# EFM32_2.net
KiCad netlist of a schematic drawn in Altium Designer
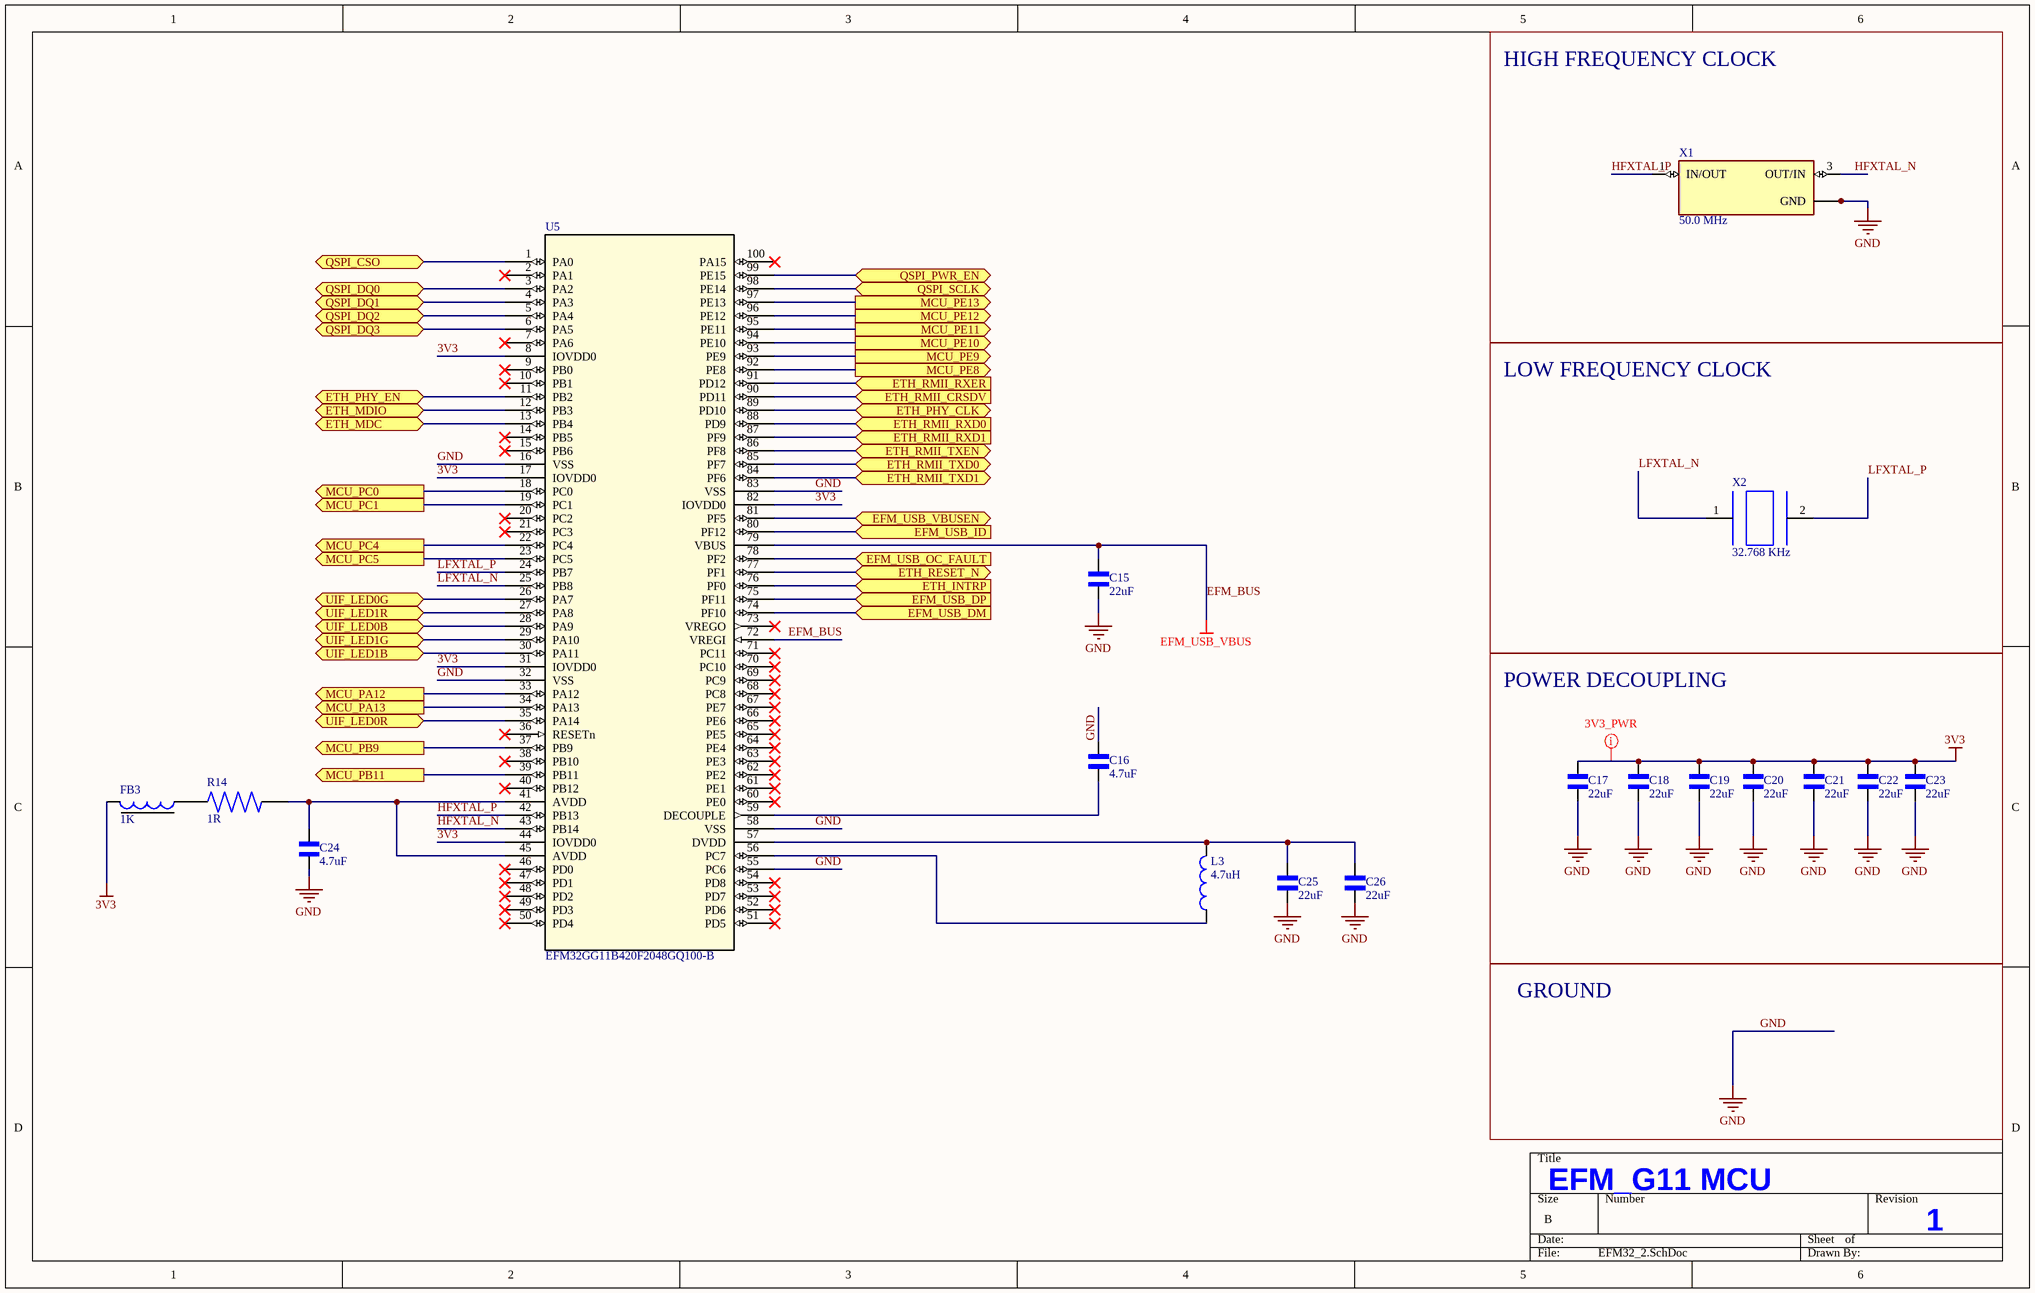
[diagram p0: EFM32_2.SchDoc]

(export (version "E")
  (design (tool "Eeschema 10.0.6"))
  (components
    (comp (ref "C15")
      (value "22uF")
      (footprint "C0603")
      (description "0603 22 uF 10 V ±20% Tolerance X5R Surface Mount Multilayer Ceramic Capacitor")
      (fields
        (field (name "MANUFACTURER") "Murata")
        (field (name "MANUFACTURER PART NUMBER") "ZRB18AR61A226ME01L")
      )
      (libsource (lib "") (part "ZRB18AR61A226ME01L_1"))
    )
    (comp (ref "C16")
      (value "4.7uF")
      (footprint "C0603")
      (description "Cap Ceramic 4.7uF 10V X5R 10% Pad SMD 0603 85C T/R")
      (fields
        (field (name "MANUFACTURER") "Samsung")
        (field (name "MANUFACTURER PART NUMBER") "CL10A475KP8NNNC")
      )
      (libsource (lib "nnts") (part "CL10A475KP8NNNC"))
    )
    (comp (ref "C17")
      (value "22uF")
      (footprint "C0603")
      (description "0603 22 uF 10 V ±20% Tolerance X5R Surface Mount Multilayer Ceramic Capacitor")
      (fields
        (field (name "MANUFACTURER") "Murata")
        (field (name "MANUFACTURER PART NUMBER") "ZRB18AR61A226ME01L")
      )
      (libsource (lib "") (part "ZRB18AR61A226ME01L_1"))
    )
    (comp (ref "C18")
      (value "22uF")
      (footprint "C0603")
      (description "0603 22 uF 10 V ±20% Tolerance X5R Surface Mount Multilayer Ceramic Capacitor")
      (fields
        (field (name "MANUFACTURER") "Murata")
        (field (name "MANUFACTURER PART NUMBER") "ZRB18AR61A226ME01L")
      )
      (libsource (lib "") (part "ZRB18AR61A226ME01L_1"))
    )
    (comp (ref "C19")
      (value "22uF")
      (footprint "C0603")
      (description "0603 22 uF 10 V ±20% Tolerance X5R Surface Mount Multilayer Ceramic Capacitor")
      (fields
        (field (name "MANUFACTURER") "Murata")
        (field (name "MANUFACTURER PART NUMBER") "ZRB18AR61A226ME01L")
      )
      (libsource (lib "nnts") (part "ZRB18AR61A226ME01L"))
    )
    (comp (ref "C20")
      (value "22uF")
      (footprint "C0603")
      (description "0603 22 uF 10 V ±20% Tolerance X5R Surface Mount Multilayer Ceramic Capacitor")
      (fields
        (field (name "MANUFACTURER") "Murata")
        (field (name "MANUFACTURER PART NUMBER") "ZRB18AR61A226ME01L")
      )
      (libsource (lib "nnts") (part "ZRB18AR61A226ME01L"))
    )
    (comp (ref "C21")
      (value "22uF")
      (footprint "C0603")
      (description "0603 22 uF 10 V ±20% Tolerance X5R Surface Mount Multilayer Ceramic Capacitor")
      (fields
        (field (name "MANUFACTURER") "Murata")
        (field (name "MANUFACTURER PART NUMBER") "ZRB18AR61A226ME01L")
      )
      (libsource (lib "nnts") (part "ZRB18AR61A226ME01L"))
    )
    (comp (ref "C22")
      (value "22uF")
      (footprint "C0603")
      (description "0603 22 uF 10 V ±20% Tolerance X5R Surface Mount Multilayer Ceramic Capacitor")
      (fields
        (field (name "MANUFACTURER") "Murata")
        (field (name "MANUFACTURER PART NUMBER") "ZRB18AR61A226ME01L")
      )
      (libsource (lib "nnts") (part "ZRB18AR61A226ME01L"))
    )
    (comp (ref "C23")
      (value "22uF")
      (footprint "C0603")
      (description "0603 22 uF 10 V ±20% Tolerance X5R Surface Mount Multilayer Ceramic Capacitor")
      (fields
        (field (name "MANUFACTURER") "Murata")
        (field (name "MANUFACTURER PART NUMBER") "ZRB18AR61A226ME01L")
      )
      (libsource (lib "nnts") (part "ZRB18AR61A226ME01L"))
    )
    (comp (ref "C24")
      (value "4.7uF")
      (footprint "C0603")
      (description "Cap Ceramic 4.7uF 10V X5R 10% Pad SMD 0603 85C T/R")
      (fields
        (field (name "MANUFACTURER") "Samsung")
        (field (name "MANUFACTURER PART NUMBER") "CL10A475KP8NNNC")
      )
      (libsource (lib "") (part "CL10A475KP8NNNC_1"))
    )
    (comp (ref "C25")
      (value "22uF")
      (footprint "C0603")
      (description "0603 22 uF 10 V ±20% Tolerance X5R Surface Mount Multilayer Ceramic Capacitor")
      (fields
        (field (name "MANUFACTURER") "Murata")
        (field (name "MANUFACTURER PART NUMBER") "ZRB18AR61A226ME01L")
      )
      (libsource (lib "nnts") (part "ZRB18AR61A226ME01L"))
    )
    (comp (ref "C26")
      (value "22uF")
      (footprint "C0603")
      (description "0603 22 uF 10 V ±20% Tolerance X5R Surface Mount Multilayer Ceramic Capacitor")
      (fields
        (field (name "MANUFACTURER") "Murata")
        (field (name "MANUFACTURER PART NUMBER") "ZRB18AR61A226ME01L")
      )
      (libsource (lib "nnts") (part "ZRB18AR61A226ME01L"))
    )
    (comp (ref "FB3")
      (value "1K")
      (footprint "FB0402")
      (description "FERRITE BEAD 1 KOHM 0402 1LN")
      (fields
        (field (name "MANUFACTURER") "Murata")
        (field (name "MANUFACTURER PART NUMBER") "BLM15AG102SH1D")
      )
      (libsource (lib "nnts") (part "BLM15AG102SH1D"))
    )
    (comp (ref "L3")
      (value "4.7uH")
      (footprint "L0805")
      (description "Inductor with Inductance: 4.7uH Tol. +/-20%, Package: 0805 (2012)")
      (fields (field (name "MP") "LQM21PN4R7MGRB") (field (name "MF") "Murata"))
      (libsource (lib "nnts") (part "LQM21PN4R7MGRB"))
    )
    (comp (ref "R14")
      (value "1R")
      (footprint "R0402 Vishay")
      (description "RES SMD 1 OHM 1% 1/16W 0402")
      (fields
        (field (name "MANUFACTURER") "Vishay")
        (field (name "MANUFACTURER PART NUMBER") "CRCW04021R00FNED")
      )
      (libsource (lib "nnts") (part "CRCW04021R00FNED"))
    )
    (comp (ref "U5")
      (value "EFM32GG11B420F2048GQ100-B")
      (footprint "TQFP100-14X14-0p")
      (description "MCU 32-bit ARM Cortex M4 RISC 2MB Flash 3.3V 100-Pin TQFP Tray")
      (fields (field (name "MANUFACTURER") "Silicon Labs"))
      (libsource (lib "nnts") (part "EFM32GG11B420F2048GQ100-B"))
    )
    (comp (ref "X1")
      (value "50.0 MHz")
      (footprint "XTAL_ECS-500-8-47B-CWY-TR")
      (description "CRYSTAL 50.0000MHZ 8PF SMD")
      (fields (field (name "MF") "ECS Inc.") (field (name "MP") "ECS-500-8-47B-CWY-TR"))
      (libsource (lib "nnts") (part "ECS-500-8-47B-CWY-TR"))
    )
    (comp (ref "X2")
      (value "32.768 KHz")
      (footprint "XTAL_FC-135_32.7680KA-A0")
      (description "32.768kHz Â±20ppm Crystal 12.5pF 70 kOhms 2-SMD, No Lead")
      (fields (field (name "MP") "FC-135 32.7680KA-A0") (field (name "MF") "EPSON"))
      (libsource (lib "nnts") (part "FC-135_32.7680KA-A0"))
    )
  )
  (nets
    (net (code "1") (name "/EFM_USB_DM") (class "Default")
      (node (ref "U5") (pin "74") (pinfunction "PF10_74") (pintype "bidirectional"))
    )
    (net (code "2") (name "/EFM_USB_DP") (class "Default")
      (node (ref "U5") (pin "75") (pinfunction "PF11_75") (pintype "bidirectional"))
    )
    (net (code "3") (name "/EFM_USB_ID") (class "Default")
      (node (ref "U5") (pin "80") (pinfunction "PF12_80") (pintype "bidirectional"))
    )
    (net (code "4") (name "/EFM_USB_OC_FAULT") (class "Default")
      (node (ref "U5") (pin "78") (pinfunction "PF2_78") (pintype "bidirectional"))
    )
    (net (code "5") (name "/EFM_USB_VBUSEN") (class "Default")
      (node (ref "U5") (pin "81") (pinfunction "PF5_81") (pintype "bidirectional"))
    )
    (net (code "6") (name "/ETH_INTRP") (class "Default")
      (node (ref "U5") (pin "76") (pinfunction "PF0_76") (pintype "bidirectional"))
    )
    (net (code "7") (name "/ETH_MDC") (class "Default")
      (node (ref "U5") (pin "13") (pinfunction "PB4_13") (pintype "bidirectional"))
    )
    (net (code "8") (name "/ETH_MDIO") (class "Default")
      (node (ref "U5") (pin "12") (pinfunction "PB3_12") (pintype "bidirectional"))
    )
    (net (code "9") (name "/ETH_PHY_CLK") (class "Default")
      (node (ref "U5") (pin "89") (pinfunction "PD10_89") (pintype "bidirectional"))
    )
    (net (code "10") (name "/ETH_PHY_EN") (class "Default")
      (node (ref "U5") (pin "11") (pinfunction "PB2_11") (pintype "bidirectional"))
    )
    (net (code "11") (name "/ETH_RESET_N") (class "Default")
      (node (ref "U5") (pin "77") (pinfunction "PF1_77") (pintype "bidirectional"))
    )
    (net (code "12") (name "/ETH_RMII_CRSDV") (class "Default")
      (node (ref "U5") (pin "90") (pinfunction "PD11_90") (pintype "bidirectional"))
    )
    (net (code "13") (name "/ETH_RMII_RXD0") (class "Default")
      (node (ref "U5") (pin "88") (pinfunction "PD9_88") (pintype "bidirectional"))
    )
    (net (code "14") (name "/ETH_RMII_RXD1") (class "Default")
      (node (ref "U5") (pin "87") (pinfunction "PF9_87") (pintype "bidirectional"))
    )
    (net (code "15") (name "/ETH_RMII_RXER") (class "Default")
      (node (ref "U5") (pin "91") (pinfunction "PD12_91") (pintype "bidirectional"))
    )
    (net (code "16") (name "/ETH_RMII_TXD0") (class "Default")
      (node (ref "U5") (pin "85") (pinfunction "PF7_85") (pintype "bidirectional"))
    )
    (net (code "17") (name "/ETH_RMII_TXD1") (class "Default")
      (node (ref "U5") (pin "84") (pinfunction "PF6_84") (pintype "bidirectional"))
    )
    (net (code "18") (name "/ETH_RMII_TXEN") (class "Default")
      (node (ref "U5") (pin "86") (pinfunction "PF8_86") (pintype "bidirectional"))
    )
    (net (code "19") (name "/HFXTAL_N") (class "Default")
      (node (ref "U5") (pin "43") (pinfunction "PB14_43") (pintype "bidirectional"))
      (node (ref "X1") (pin "3") (pinfunction "OUT/IN_3") (pintype "bidirectional"))
    )
    (net (code "20") (name "/HFXTAL_P") (class "Default")
      (node (ref "U5") (pin "42") (pinfunction "PB13_42") (pintype "bidirectional"))
      (node (ref "X1") (pin "1") (pinfunction "IN/OUT_1") (pintype "bidirectional"))
    )
    (net (code "21") (name "/LFXTAL_N") (class "Default")
      (node (ref "U5") (pin "25") (pinfunction "PB8_25") (pintype "bidirectional"))
      (node (ref "X2") (pin "1") (pinfunction "1_1") (pintype "passive"))
    )
    (net (code "22") (name "/LFXTAL_P") (class "Default")
      (node (ref "U5") (pin "24") (pinfunction "PB7_24") (pintype "bidirectional"))
      (node (ref "X2") (pin "2") (pinfunction "2_2") (pintype "passive"))
    )
    (net (code "23") (name "/MCU_PA12") (class "Default")
      (node (ref "U5") (pin "33") (pinfunction "PA12_33") (pintype "bidirectional"))
    )
    (net (code "24") (name "/MCU_PA13") (class "Default")
      (node (ref "U5") (pin "34") (pinfunction "PA13_34") (pintype "bidirectional"))
    )
    (net (code "25") (name "/MCU_PB9") (class "Default")
      (node (ref "U5") (pin "37") (pinfunction "PB9_37") (pintype "bidirectional"))
    )
    (net (code "26") (name "/MCU_PB11") (class "Default")
      (node (ref "U5") (pin "39") (pinfunction "PB11_39") (pintype "bidirectional"))
    )
    (net (code "27") (name "/MCU_PC0") (class "Default")
      (node (ref "U5") (pin "18") (pinfunction "PC0_18") (pintype "bidirectional"))
    )
    (net (code "28") (name "/MCU_PC1") (class "Default")
      (node (ref "U5") (pin "19") (pinfunction "PC1_19") (pintype "bidirectional"))
    )
    (net (code "29") (name "/MCU_PC4") (class "Default")
      (node (ref "U5") (pin "22") (pinfunction "PC4_22") (pintype "bidirectional"))
    )
    (net (code "30") (name "/MCU_PC5") (class "Default")
      (node (ref "U5") (pin "23") (pinfunction "PC5_23") (pintype "bidirectional"))
    )
    (net (code "31") (name "/MCU_PE8") (class "Default")
      (node (ref "U5") (pin "92") (pinfunction "PE8_92") (pintype "bidirectional"))
    )
    (net (code "32") (name "/MCU_PE9") (class "Default")
      (node (ref "U5") (pin "93") (pinfunction "PE9_93") (pintype "bidirectional"))
    )
    (net (code "33") (name "/MCU_PE10") (class "Default")
      (node (ref "U5") (pin "94") (pinfunction "PE10_94") (pintype "bidirectional"))
    )
    (net (code "34") (name "/MCU_PE11") (class "Default")
      (node (ref "U5") (pin "95") (pinfunction "PE11_95") (pintype "bidirectional"))
    )
    (net (code "35") (name "/MCU_PE12") (class "Default")
      (node (ref "U5") (pin "96") (pinfunction "PE12_96") (pintype "bidirectional"))
    )
    (net (code "36") (name "/MCU_PE13") (class "Default")
      (node (ref "U5") (pin "97") (pinfunction "PE13_97") (pintype "bidirectional"))
    )
    (net (code "37") (name "/QSPI_CSO") (class "Default")
      (node (ref "U5") (pin "1") (pinfunction "PA0_1") (pintype "bidirectional"))
    )
    (net (code "38") (name "/QSPI_DQ0") (class "Default")
      (node (ref "U5") (pin "3") (pinfunction "PA2_3") (pintype "bidirectional"))
    )
    (net (code "39") (name "/QSPI_DQ1") (class "Default")
      (node (ref "U5") (pin "4") (pinfunction "PA3_4") (pintype "bidirectional"))
    )
    (net (code "40") (name "/QSPI_DQ2") (class "Default")
      (node (ref "U5") (pin "5") (pinfunction "PA4_5") (pintype "bidirectional"))
    )
    (net (code "41") (name "/QSPI_DQ3") (class "Default")
      (node (ref "U5") (pin "6") (pinfunction "PA5_6") (pintype "bidirectional"))
    )
    (net (code "42") (name "/QSPI_PWR_EN") (class "Default")
      (node (ref "U5") (pin "99") (pinfunction "PE15_99") (pintype "bidirectional"))
    )
    (net (code "43") (name "/QSPI_SCLK") (class "Default")
      (node (ref "U5") (pin "98") (pinfunction "PE14_98") (pintype "bidirectional"))
    )
    (net (code "44") (name "/UIF_LED0B") (class "Default")
      (node (ref "U5") (pin "28") (pinfunction "PA9_28") (pintype "bidirectional"))
    )
    (net (code "45") (name "/UIF_LED0G") (class "Default")
      (node (ref "U5") (pin "26") (pinfunction "PA7_26") (pintype "bidirectional"))
    )
    (net (code "46") (name "/UIF_LED0R") (class "Default")
      (node (ref "U5") (pin "35") (pinfunction "PA14_35") (pintype "bidirectional"))
    )
    (net (code "47") (name "/UIF_LED1B") (class "Default")
      (node (ref "U5") (pin "30") (pinfunction "PA11_30") (pintype "bidirectional"))
    )
    (net (code "48") (name "/UIF_LED1G") (class "Default")
      (node (ref "U5") (pin "29") (pinfunction "PA10_29") (pintype "bidirectional"))
    )
    (net (code "49") (name "/UIF_LED1R") (class "Default")
      (node (ref "U5") (pin "27") (pinfunction "PA8_27") (pintype "bidirectional"))
    )
    (net (code "50") (name "3V3") (class "Default")
      (node (ref "C17") (pin "2") (pinfunction "2_2") (pintype "passive"))
      (node (ref "C18") (pin "2") (pinfunction "2_2") (pintype "passive"))
      (node (ref "C19") (pin "1") (pinfunction "1_1") (pintype "passive"))
      (node (ref "C20") (pin "1") (pinfunction "1_1") (pintype "passive"))
      (node (ref "C21") (pin "1") (pinfunction "1_1") (pintype "passive"))
      (node (ref "C22") (pin "1") (pinfunction "1_1") (pintype "passive"))
      (node (ref "C23") (pin "1") (pinfunction "1_1") (pintype "passive"))
      (node (ref "FB3") (pin "2") (pinfunction "2_2") (pintype "passive"))
      (node (ref "U5") (pin "17") (pinfunction "IOVDD0_17") (pintype "power_in"))
      (node (ref "U5") (pin "31") (pinfunction "IOVDD0_31") (pintype "power_in"))
      (node (ref "U5") (pin "44") (pinfunction "IOVDD0_44") (pintype "power_in"))
      (node (ref "U5") (pin "8") (pinfunction "IOVDD0_8") (pintype "power_in"))
      (node (ref "U5") (pin "82") (pinfunction "IOVDD0_82") (pintype "power_in"))
    )
    (net (code "51") (name "EFM_USB_VBUS") (class "Default")
      (node (ref "C15") (pin "2") (pinfunction "2_2") (pintype "passive"))
      (node (ref "U5") (pin "72") (pinfunction "VREGI_72") (pintype "input"))
      (node (ref "U5") (pin "79") (pinfunction "VBUS_79") (pintype "power_in"))
    )
    (net (code "52") (name "GND") (class "Default")
      (node (ref "C15") (pin "1") (pinfunction "1_1") (pintype "passive"))
      (node (ref "C16") (pin "1") (pinfunction "1_1") (pintype "passive"))
      (node (ref "C17") (pin "1") (pinfunction "1_1") (pintype "passive"))
      (node (ref "C18") (pin "1") (pinfunction "1_1") (pintype "passive"))
      (node (ref "C19") (pin "2") (pinfunction "2_2") (pintype "passive"))
      (node (ref "C20") (pin "2") (pinfunction "2_2") (pintype "passive"))
      (node (ref "C21") (pin "2") (pinfunction "2_2") (pintype "passive"))
      (node (ref "C22") (pin "2") (pinfunction "2_2") (pintype "passive"))
      (node (ref "C23") (pin "2") (pinfunction "2_2") (pintype "passive"))
      (node (ref "C24") (pin "1") (pinfunction "1_1") (pintype "passive"))
      (node (ref "C25") (pin "2") (pinfunction "2_2") (pintype "passive"))
      (node (ref "C26") (pin "2") (pinfunction "2_2") (pintype "passive"))
      (node (ref "U5") (pin "16") (pinfunction "VSS_16") (pintype "power_in"))
      (node (ref "U5") (pin "32") (pinfunction "VSS_32") (pintype "power_in"))
      (node (ref "U5") (pin "55") (pinfunction "PC6_55") (pintype "bidirectional"))
      (node (ref "U5") (pin "58") (pinfunction "VSS_58") (pintype "power_in"))
      (node (ref "U5") (pin "83") (pinfunction "VSS_83") (pintype "power_in"))
      (node (ref "X1") (pin "2") (pinfunction "GND_2") (pintype "power_in"))
      (node (ref "X1") (pin "4") (pinfunction "GND_4") (pintype "power_in"))
    )
    (net (code "53") (name "Net-(C24-Pad2)") (class "Default")
      (node (ref "C24") (pin "2") (pinfunction "2_2") (pintype "passive"))
      (node (ref "R14") (pin "1") (pinfunction "1_1") (pintype "passive"))
      (node (ref "U5") (pin "41") (pinfunction "AVDD_41") (pintype "power_in"))
      (node (ref "U5") (pin "45") (pinfunction "AVDD_45") (pintype "power_in"))
    )
    (net (code "54") (name "Net-(U5-DECOUPLE)") (class "Default")
      (node (ref "C16") (pin "2") (pinfunction "2_2") (pintype "passive"))
      (node (ref "U5") (pin "59") (pinfunction "DECOUPLE_59") (pintype "output"))
    )
    (net (code "55") (name "Net-(U5-DVDD)") (class "Default")
      (node (ref "C25") (pin "1") (pinfunction "1_1") (pintype "passive"))
      (node (ref "C26") (pin "1") (pinfunction "1_1") (pintype "passive"))
      (node (ref "L3") (pin "2") (pinfunction "2_2") (pintype "passive"))
      (node (ref "U5") (pin "57") (pinfunction "DVDD_57") (pintype "power_in"))
    )
    (net (code "56") (name "Net-(U5-PC7)") (class "Default")
      (node (ref "L3") (pin "1") (pinfunction "1_1") (pintype "passive"))
      (node (ref "U5") (pin "56") (pinfunction "PC7_56") (pintype "bidirectional"))
    )
    (net (code "57") (name "unconnected-(FB3-Pad1)") (class "Default")
      (node (ref "FB3") (pin "1") (pinfunction "1_1") (pintype "passive"))
    )
    (net (code "58") (name "unconnected-(R14-Pad2)") (class "Default")
      (node (ref "R14") (pin "2") (pinfunction "2_2") (pintype "passive"))
    )
    (net (code "59") (name "unconnected-(U5-PA1-Pad2)") (class "Default")
      (node (ref "U5") (pin "2") (pinfunction "PA1_2") (pintype "bidirectional+no_connect"))
    )
    (net (code "60") (name "unconnected-(U5-PA6-Pad7)") (class "Default")
      (node (ref "U5") (pin "7") (pinfunction "PA6_7") (pintype "bidirectional+no_connect"))
    )
    (net (code "61") (name "unconnected-(U5-PA15-Pad100)") (class "Default")
      (node (ref "U5") (pin "100") (pinfunction "PA15_100") (pintype "bidirectional+no_connect"))
    )
    (net (code "62") (name "unconnected-(U5-PB0-Pad9)") (class "Default")
      (node (ref "U5") (pin "9") (pinfunction "PB0_9") (pintype "bidirectional+no_connect"))
    )
    (net (code "63") (name "unconnected-(U5-PB1-Pad10)") (class "Default")
      (node (ref "U5") (pin "10") (pinfunction "PB1_10") (pintype "bidirectional+no_connect"))
    )
    (net (code "64") (name "unconnected-(U5-PB5-Pad14)") (class "Default")
      (node (ref "U5") (pin "14") (pinfunction "PB5_14") (pintype "bidirectional+no_connect"))
    )
    (net (code "65") (name "unconnected-(U5-PB6-Pad15)") (class "Default")
      (node (ref "U5") (pin "15") (pinfunction "PB6_15") (pintype "bidirectional+no_connect"))
    )
    (net (code "66") (name "unconnected-(U5-PB10-Pad38)") (class "Default")
      (node (ref "U5") (pin "38") (pinfunction "PB10_38") (pintype "bidirectional+no_connect"))
    )
    (net (code "67") (name "unconnected-(U5-PB12-Pad40)") (class "Default")
      (node (ref "U5") (pin "40") (pinfunction "PB12_40") (pintype "bidirectional+no_connect"))
    )
    (net (code "68") (name "unconnected-(U5-PC2-Pad20)") (class "Default")
      (node (ref "U5") (pin "20") (pinfunction "PC2_20") (pintype "bidirectional+no_connect"))
    )
    (net (code "69") (name "unconnected-(U5-PC3-Pad21)") (class "Default")
      (node (ref "U5") (pin "21") (pinfunction "PC3_21") (pintype "bidirectional+no_connect"))
    )
    (net (code "70") (name "unconnected-(U5-PC8-Pad68)") (class "Default")
      (node (ref "U5") (pin "68") (pinfunction "PC8_68") (pintype "bidirectional+no_connect"))
    )
    (net (code "71") (name "unconnected-(U5-PC9-Pad69)") (class "Default")
      (node (ref "U5") (pin "69") (pinfunction "PC9_69") (pintype "bidirectional+no_connect"))
    )
    (net (code "72") (name "unconnected-(U5-PC10-Pad70)") (class "Default")
      (node (ref "U5") (pin "70") (pinfunction "PC10_70") (pintype "bidirectional+no_connect"))
    )
    (net (code "73") (name "unconnected-(U5-PC11-Pad71)") (class "Default")
      (node (ref "U5") (pin "71") (pinfunction "PC11_71") (pintype "bidirectional+no_connect"))
    )
    (net (code "74") (name "unconnected-(U5-PD0-Pad46)") (class "Default")
      (node (ref "U5") (pin "46") (pinfunction "PD0_46") (pintype "bidirectional+no_connect"))
    )
    (net (code "75") (name "unconnected-(U5-PD1-Pad47)") (class "Default")
      (node (ref "U5") (pin "47") (pinfunction "PD1_47") (pintype "bidirectional+no_connect"))
    )
    (net (code "76") (name "unconnected-(U5-PD2-Pad48)") (class "Default")
      (node (ref "U5") (pin "48") (pinfunction "PD2_48") (pintype "bidirectional+no_connect"))
    )
    (net (code "77") (name "unconnected-(U5-PD3-Pad49)") (class "Default")
      (node (ref "U5") (pin "49") (pinfunction "PD3_49") (pintype "bidirectional+no_connect"))
    )
    (net (code "78") (name "unconnected-(U5-PD4-Pad50)") (class "Default")
      (node (ref "U5") (pin "50") (pinfunction "PD4_50") (pintype "bidirectional+no_connect"))
    )
    (net (code "79") (name "unconnected-(U5-PD5-Pad51)") (class "Default")
      (node (ref "U5") (pin "51") (pinfunction "PD5_51") (pintype "bidirectional+no_connect"))
    )
    (net (code "80") (name "unconnected-(U5-PD6-Pad52)") (class "Default")
      (node (ref "U5") (pin "52") (pinfunction "PD6_52") (pintype "bidirectional+no_connect"))
    )
    (net (code "81") (name "unconnected-(U5-PD7-Pad53)") (class "Default")
      (node (ref "U5") (pin "53") (pinfunction "PD7_53") (pintype "bidirectional+no_connect"))
    )
    (net (code "82") (name "unconnected-(U5-PD8-Pad54)") (class "Default")
      (node (ref "U5") (pin "54") (pinfunction "PD8_54") (pintype "bidirectional+no_connect"))
    )
    (net (code "83") (name "unconnected-(U5-PE0-Pad60)") (class "Default")
      (node (ref "U5") (pin "60") (pinfunction "PE0_60") (pintype "bidirectional+no_connect"))
    )
    (net (code "84") (name "unconnected-(U5-PE1-Pad61)") (class "Default")
      (node (ref "U5") (pin "61") (pinfunction "PE1_61") (pintype "bidirectional+no_connect"))
    )
    (net (code "85") (name "unconnected-(U5-PE2-Pad62)") (class "Default")
      (node (ref "U5") (pin "62") (pinfunction "PE2_62") (pintype "bidirectional+no_connect"))
    )
    (net (code "86") (name "unconnected-(U5-PE3-Pad63)") (class "Default")
      (node (ref "U5") (pin "63") (pinfunction "PE3_63") (pintype "bidirectional+no_connect"))
    )
    (net (code "87") (name "unconnected-(U5-PE4-Pad64)") (class "Default")
      (node (ref "U5") (pin "64") (pinfunction "PE4_64") (pintype "bidirectional+no_connect"))
    )
    (net (code "88") (name "unconnected-(U5-PE5-Pad65)") (class "Default")
      (node (ref "U5") (pin "65") (pinfunction "PE5_65") (pintype "bidirectional+no_connect"))
    )
    (net (code "89") (name "unconnected-(U5-PE6-Pad66)") (class "Default")
      (node (ref "U5") (pin "66") (pinfunction "PE6_66") (pintype "bidirectional+no_connect"))
    )
    (net (code "90") (name "unconnected-(U5-PE7-Pad67)") (class "Default")
      (node (ref "U5") (pin "67") (pinfunction "PE7_67") (pintype "bidirectional+no_connect"))
    )
    (net (code "91") (name "unconnected-(U5-RESETn-Pad36)") (class "Default")
      (node (ref "U5") (pin "36") (pinfunction "RESETn_36") (pintype "input+no_connect"))
    )
    (net (code "92") (name "unconnected-(U5-VREGO-Pad73)") (class "Default")
      (node (ref "U5") (pin "73") (pinfunction "VREGO_73") (pintype "output+no_connect"))
    )
  )
)
